# aspirin.net
KiCad netlist of a schematic drawn in EAGLE
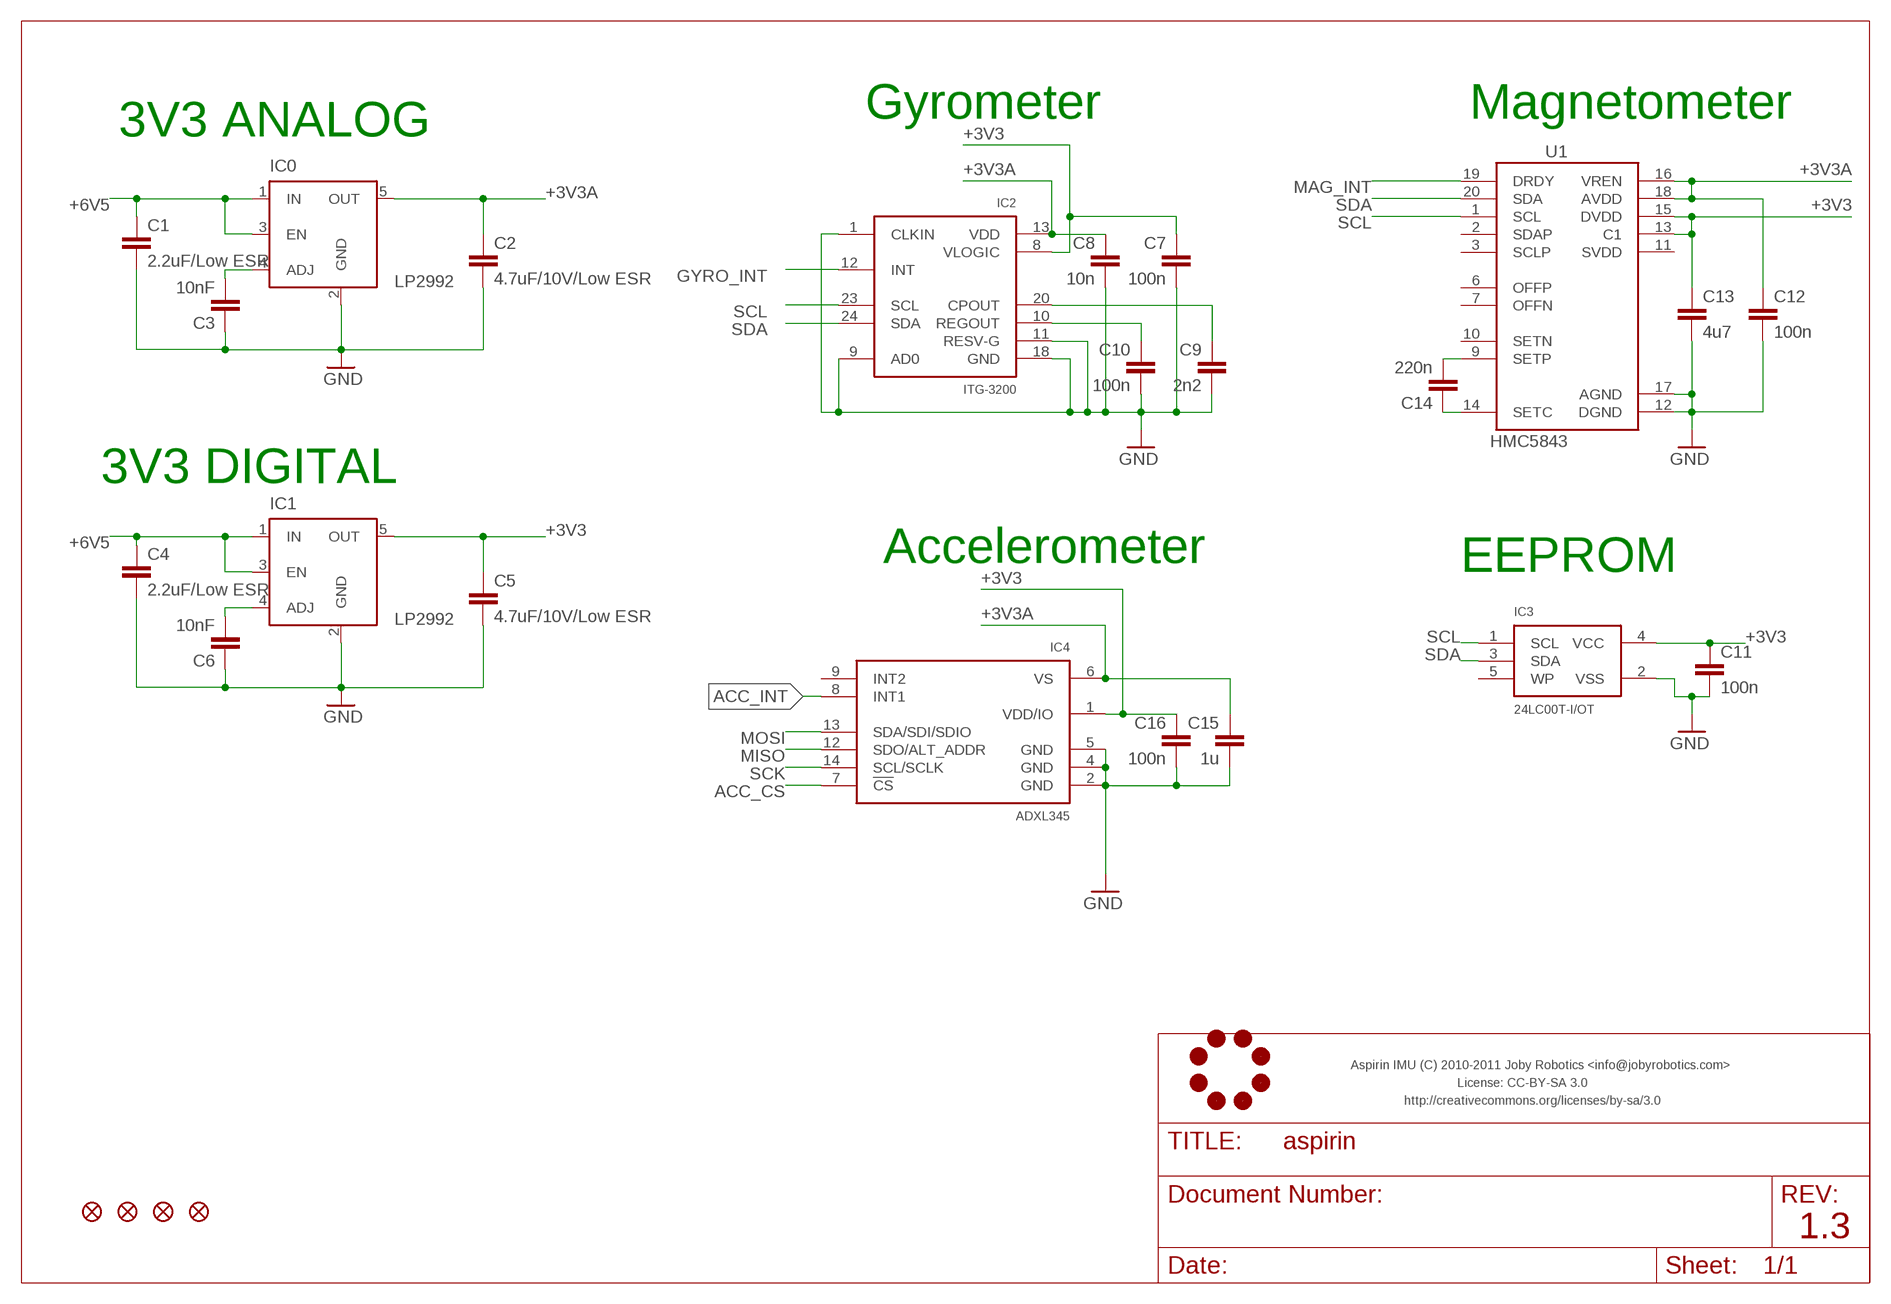
[diagram p0: schematic, sheet 1]

(export (version "E")
  (design (tool "Eeschema 10.0.6"))
  (components
    (comp (ref "C1")
      (value "2.2uF/Low ESR")
      (footprint "eagle-import:0603-CAP")
      (libsource (lib "eagle-import") (part "CAPACITOR-0603"))
    )
    (comp (ref "C2")
      (value "4.7uF/10V/Low ESR")
      (footprint "eagle-import:0402-CAP")
      (libsource (lib "eagle-import") (part "CAPACITOR-0402"))
    )
    (comp (ref "C3")
      (value "10nF")
      (footprint "eagle-import:0402-CAP")
      (libsource (lib "eagle-import") (part "CAPACITOR-0402"))
    )
    (comp (ref "C4")
      (value "2.2uF/Low ESR")
      (footprint "eagle-import:0603-CAP")
      (libsource (lib "eagle-import") (part "CAPACITOR-0603"))
    )
    (comp (ref "C5")
      (value "4.7uF/10V/Low ESR")
      (footprint "eagle-import:0402-CAP")
      (libsource (lib "eagle-import") (part "CAPACITOR-0402"))
    )
    (comp (ref "C6")
      (value "10nF")
      (footprint "eagle-import:0402-CAP")
      (libsource (lib "eagle-import") (part "CAPACITOR-0402"))
    )
    (comp (ref "C7")
      (value "100n")
      (footprint "eagle-import:0402-CAP")
      (libsource (lib "eagle-import") (part "CAPACITOR-0402"))
    )
    (comp (ref "C8")
      (value "10n")
      (footprint "eagle-import:0402-CAP")
      (libsource (lib "eagle-import") (part "CAPACITOR-0402"))
    )
    (comp (ref "C9")
      (value "2n2")
      (footprint "eagle-import:0402-CAP")
      (libsource (lib "eagle-import") (part "CAPACITOR-0402"))
    )
    (comp (ref "C10")
      (value "100n")
      (footprint "eagle-import:0402-CAP")
      (libsource (lib "eagle-import") (part "CAPACITOR-0402"))
    )
    (comp (ref "C11")
      (value "100n")
      (footprint "eagle-import:0402-CAP")
      (libsource (lib "eagle-import") (part "CAPACITOR-0402"))
    )
    (comp (ref "C12")
      (value "100n")
      (footprint "eagle-import:0402-CAP")
      (libsource (lib "eagle-import") (part "CAPACITOR-0402"))
    )
    (comp (ref "C13")
      (value "4u7")
      (footprint "eagle-import:0402-CAP")
      (libsource (lib "eagle-import") (part "CAPACITOR-0402"))
    )
    (comp (ref "C14")
      (value "220n")
      (footprint "eagle-import:0402-CAP")
      (libsource (lib "eagle-import") (part "CAPACITOR-0402"))
    )
    (comp (ref "C15")
      (value "1u")
      (footprint "eagle-import:0402-CAP")
      (libsource (lib "eagle-import") (part "CAPACITOR-0402"))
    )
    (comp (ref "C16")
      (value "100n")
      (footprint "eagle-import:0402-CAP")
      (libsource (lib "eagle-import") (part "CAPACITOR-0402"))
    )
    (comp (ref "IC0")
      (value "LP2992")
      (footprint "eagle-import:SOT23-5")
      (libsource (lib "eagle-import") (part "MIC5219BM5"))
    )
    (comp (ref "IC1")
      (value "LP2992")
      (footprint "eagle-import:SOT23-5")
      (libsource (lib "eagle-import") (part "MIC5219BM5"))
    )
    (comp (ref "IC2")
      (value "ITG-3200")
      (footprint "eagle-import:QFN24-WITH-AXES")
      (libsource (lib "eagle-import") (part "ITG-3200-AX"))
    )
    (comp (ref "IC3")
      (value "24LC00T-I/OT")
      (footprint "eagle-import:SOT23-5")
      (libsource (lib "eagle-import") (part "I2C_EEPROM-SOT23-5"))
    )
    (comp (ref "IC4")
      (value "ADXL345")
      (footprint "eagle-import:LGA-14")
      (libsource (lib "eagle-import") (part "ADXL345"))
    )
    (comp (ref "JL2")
      (value "JOBY_LOGO-6MIL")
      (footprint "eagle-import:JOBY_LOGO_6MIL")
      (libsource (lib "eagle-import") (part "JOBY_LOGO-6MIL"))
    )
    (comp (ref "JP1")
      (value "FIDUCIAL1X2")
      (footprint "eagle-import:FIDUCIAL-1X2")
      (libsource (lib "eagle-import") (part "FIDUCIAL1X2"))
    )
    (comp (ref "JP2")
      (value "FIDUCIAL1X2")
      (footprint "eagle-import:FIDUCIAL-1X2")
      (libsource (lib "eagle-import") (part "FIDUCIAL1X2"))
    )
    (comp (ref "JP3")
      (value "FIDUCIAL1X2")
      (footprint "eagle-import:FIDUCIAL-1X2")
      (libsource (lib "eagle-import") (part "FIDUCIAL1X2"))
    )
    (comp (ref "JP4")
      (value "FIDUCIAL1X2")
      (footprint "eagle-import:FIDUCIAL-1X2")
      (libsource (lib "eagle-import") (part "FIDUCIAL1X2"))
    )
    (comp (ref "U1")
      (value "HMC5843")
      (footprint "eagle-import:LPCC20-HMC5843")
      (libsource (lib "eagle-import") (part "HMC5843"))
    )
  )
  (nets
    (net (code "1") (name "/+3V3") (class "Default")
      (node (ref "C11") (pin "P$1") (pinfunction "1_P$1") (pintype "passive"))
      (node (ref "C13") (pin "P$1") (pinfunction "1_P$1") (pintype "passive"))
      (node (ref "C16") (pin "P$1") (pinfunction "1_P$1") (pintype "passive"))
      (node (ref "C5") (pin "P$1") (pinfunction "1_P$1") (pintype "passive"))
      (node (ref "C7") (pin "P$1") (pinfunction "1_P$1") (pintype "passive"))
      (node (ref "IC1") (pin "5") (pinfunction "OUT_5") (pintype "output"))
      (node (ref "IC2") (pin "8") (pinfunction "VLOGIC_8") (pintype "bidirectional"))
      (node (ref "IC3") (pin "4") (pinfunction "VCC_4") (pintype "bidirectional"))
      (node (ref "IC4") (pin "1") (pinfunction "VDD/IO_1") (pintype "bidirectional"))
      (node (ref "U1") (pin "13") (pinfunction "C1_13") (pintype "bidirectional"))
      (node (ref "U1") (pin "15") (pinfunction "DVDD_15") (pintype "bidirectional"))
    )
    (net (code "2") (name "/+3V3A") (class "Default")
      (node (ref "C12") (pin "P$1") (pinfunction "1_P$1") (pintype "passive"))
      (node (ref "C15") (pin "P$1") (pinfunction "1_P$1") (pintype "passive"))
      (node (ref "C2") (pin "P$1") (pinfunction "1_P$1") (pintype "passive"))
      (node (ref "C8") (pin "P$1") (pinfunction "1_P$1") (pintype "passive"))
      (node (ref "IC0") (pin "5") (pinfunction "OUT_5") (pintype "output"))
      (node (ref "IC2") (pin "13") (pinfunction "VDD_13") (pintype "bidirectional"))
      (node (ref "IC4") (pin "6") (pinfunction "VS_6") (pintype "bidirectional"))
      (node (ref "U1") (pin "16") (pinfunction "VREN_16") (pintype "bidirectional"))
      (node (ref "U1") (pin "18") (pinfunction "AVDD_18") (pintype "bidirectional"))
    )
    (net (code "3") (name "/+6V5") (class "Default")
      (node (ref "C1") (pin "P$1") (pinfunction "1_P$1") (pintype "passive"))
      (node (ref "C4") (pin "P$1") (pinfunction "1_P$1") (pintype "passive"))
      (node (ref "IC0") (pin "1") (pinfunction "IN_1") (pintype "input"))
      (node (ref "IC0") (pin "3") (pinfunction "EN_3") (pintype "input"))
      (node (ref "IC1") (pin "1") (pinfunction "IN_1") (pintype "input"))
      (node (ref "IC1") (pin "3") (pinfunction "EN_3") (pintype "input"))
    )
    (net (code "4") (name "/ACC_CS") (class "Default")
      (node (ref "IC4") (pin "7") (pinfunction "~{CS}_7") (pintype "bidirectional"))
    )
    (net (code "5") (name "/GYRO_INT") (class "Default")
      (node (ref "IC2") (pin "12") (pinfunction "INT_12") (pintype "bidirectional"))
    )
    (net (code "6") (name "/MAG_INT") (class "Default")
      (node (ref "U1") (pin "19") (pinfunction "DRDY_19") (pintype "bidirectional"))
    )
    (net (code "7") (name "/MISO") (class "Default")
      (node (ref "IC4") (pin "12") (pinfunction "SDO/ALT_ADDR_12") (pintype "bidirectional"))
    )
    (net (code "8") (name "/MOSI") (class "Default")
      (node (ref "IC4") (pin "13") (pinfunction "SDA/SDI/SDIO_13") (pintype "bidirectional"))
    )
    (net (code "9") (name "/SCK") (class "Default")
      (node (ref "IC4") (pin "14") (pinfunction "SCL/SCLK_14") (pintype "bidirectional"))
    )
    (net (code "10") (name "/SCL") (class "Default")
      (node (ref "IC2") (pin "23") (pinfunction "SCL_23") (pintype "bidirectional"))
      (node (ref "IC3") (pin "1") (pinfunction "SCL_1") (pintype "bidirectional"))
      (node (ref "U1") (pin "1") (pinfunction "SCL_1") (pintype "bidirectional"))
    )
    (net (code "11") (name "/SDA") (class "Default")
      (node (ref "IC2") (pin "24") (pinfunction "SDA_24") (pintype "bidirectional"))
      (node (ref "IC3") (pin "3") (pinfunction "SDA_3") (pintype "bidirectional"))
      (node (ref "U1") (pin "20") (pinfunction "SDA_20") (pintype "bidirectional"))
    )
    (net (code "12") (name "ACC_INT") (class "Default")
      (node (ref "IC4") (pin "8") (pinfunction "INT1_8") (pintype "bidirectional"))
    )
    (net (code "13") (name "GND") (class "Default")
      (node (ref "C1") (pin "P$2") (pinfunction "2_P$2") (pintype "passive"))
      (node (ref "C10") (pin "P$2") (pinfunction "2_P$2") (pintype "passive"))
      (node (ref "C11") (pin "P$2") (pinfunction "2_P$2") (pintype "passive"))
      (node (ref "C12") (pin "P$2") (pinfunction "2_P$2") (pintype "passive"))
      (node (ref "C13") (pin "P$2") (pinfunction "2_P$2") (pintype "passive"))
      (node (ref "C15") (pin "P$2") (pinfunction "2_P$2") (pintype "passive"))
      (node (ref "C16") (pin "P$2") (pinfunction "2_P$2") (pintype "passive"))
      (node (ref "C2") (pin "P$2") (pinfunction "2_P$2") (pintype "passive"))
      (node (ref "C3") (pin "P$1") (pinfunction "1_P$1") (pintype "passive"))
      (node (ref "C4") (pin "P$2") (pinfunction "2_P$2") (pintype "passive"))
      (node (ref "C5") (pin "P$2") (pinfunction "2_P$2") (pintype "passive"))
      (node (ref "C6") (pin "P$1") (pinfunction "1_P$1") (pintype "passive"))
      (node (ref "C7") (pin "P$2") (pinfunction "2_P$2") (pintype "passive"))
      (node (ref "C8") (pin "P$2") (pinfunction "2_P$2") (pintype "passive"))
      (node (ref "C9") (pin "P$2") (pinfunction "2_P$2") (pintype "passive"))
      (node (ref "IC0") (pin "2") (pinfunction "GND_2") (pintype "power_in"))
      (node (ref "IC1") (pin "2") (pinfunction "GND_2") (pintype "power_in"))
      (node (ref "IC2") (pin "1") (pinfunction "CLKIN_1") (pintype "bidirectional"))
      (node (ref "IC2") (pin "11") (pinfunction "RESV-G_11") (pintype "bidirectional"))
      (node (ref "IC2") (pin "18") (pinfunction "GND_18") (pintype "bidirectional"))
      (node (ref "IC2") (pin "9") (pinfunction "AD0_9") (pintype "bidirectional"))
      (node (ref "IC3") (pin "2") (pinfunction "VSS_2") (pintype "bidirectional"))
      (node (ref "IC4") (pin "2") (pinfunction "GND_2") (pintype "bidirectional"))
      (node (ref "IC4") (pin "4") (pinfunction "GND_4") (pintype "bidirectional"))
      (node (ref "IC4") (pin "5") (pinfunction "GND_5") (pintype "bidirectional"))
      (node (ref "U1") (pin "12") (pinfunction "DGND_12") (pintype "bidirectional"))
      (node (ref "U1") (pin "17") (pinfunction "AGND_17") (pintype "bidirectional"))
    )
    (net (code "14") (name "Net-(C3-2)") (class "Default")
      (node (ref "C3") (pin "P$2") (pinfunction "2_P$2") (pintype "passive"))
      (node (ref "IC0") (pin "4") (pinfunction "ADJ_4") (pintype "passive"))
    )
    (net (code "15") (name "Net-(C6-2)") (class "Default")
      (node (ref "C6") (pin "P$2") (pinfunction "2_P$2") (pintype "passive"))
      (node (ref "IC1") (pin "4") (pinfunction "ADJ_4") (pintype "passive"))
    )
    (net (code "16") (name "Net-(C9-1)") (class "Default")
      (node (ref "C9") (pin "P$1") (pinfunction "1_P$1") (pintype "passive"))
      (node (ref "IC2") (pin "20") (pinfunction "CPOUT_20") (pintype "bidirectional"))
    )
    (net (code "17") (name "Net-(C10-1)") (class "Default")
      (node (ref "C10") (pin "P$1") (pinfunction "1_P$1") (pintype "passive"))
      (node (ref "IC2") (pin "10") (pinfunction "REGOUT_10") (pintype "bidirectional"))
    )
    (net (code "18") (name "Net-(C14-1)") (class "Default")
      (node (ref "C14") (pin "P$1") (pinfunction "1_P$1") (pintype "passive"))
      (node (ref "U1") (pin "14") (pinfunction "SETC_14") (pintype "bidirectional"))
    )
    (net (code "19") (name "Net-(C14-2)") (class "Default")
      (node (ref "C14") (pin "P$2") (pinfunction "2_P$2") (pintype "passive"))
      (node (ref "U1") (pin "9") (pinfunction "SETP_9") (pintype "bidirectional"))
    )
    (net (code "20") (name "unconnected-(IC3-WP-Pad5)") (class "Default")
      (node (ref "IC3") (pin "5") (pinfunction "WP_5") (pintype "bidirectional"))
    )
    (net (code "21") (name "unconnected-(IC4-INT2-Pad9)") (class "Default")
      (node (ref "IC4") (pin "9") (pinfunction "INT2_9") (pintype "bidirectional"))
    )
    (net (code "22") (name "unconnected-(U1-OFFN-Pad7)") (class "Default")
      (node (ref "U1") (pin "7") (pinfunction "OFFN_7") (pintype "bidirectional"))
    )
    (net (code "23") (name "unconnected-(U1-OFFP-Pad6)") (class "Default")
      (node (ref "U1") (pin "6") (pinfunction "OFFP_6") (pintype "bidirectional"))
    )
    (net (code "24") (name "unconnected-(U1-SCLP-Pad3)") (class "Default")
      (node (ref "U1") (pin "3") (pinfunction "SCLP_3") (pintype "bidirectional"))
    )
    (net (code "25") (name "unconnected-(U1-SDAP-Pad2)") (class "Default")
      (node (ref "U1") (pin "2") (pinfunction "SDAP_2") (pintype "bidirectional"))
    )
    (net (code "26") (name "unconnected-(U1-SETN-Pad10)") (class "Default")
      (node (ref "U1") (pin "10") (pinfunction "SETN_10") (pintype "bidirectional"))
    )
    (net (code "27") (name "unconnected-(U1-SVDD-Pad11)") (class "Default")
      (node (ref "U1") (pin "11") (pinfunction "SVDD_11") (pintype "bidirectional"))
    )
  )
)
